# Grove-LED_Socket_Kit_v1_3.net
KiCad netlist of a schematic drawn in EAGLE
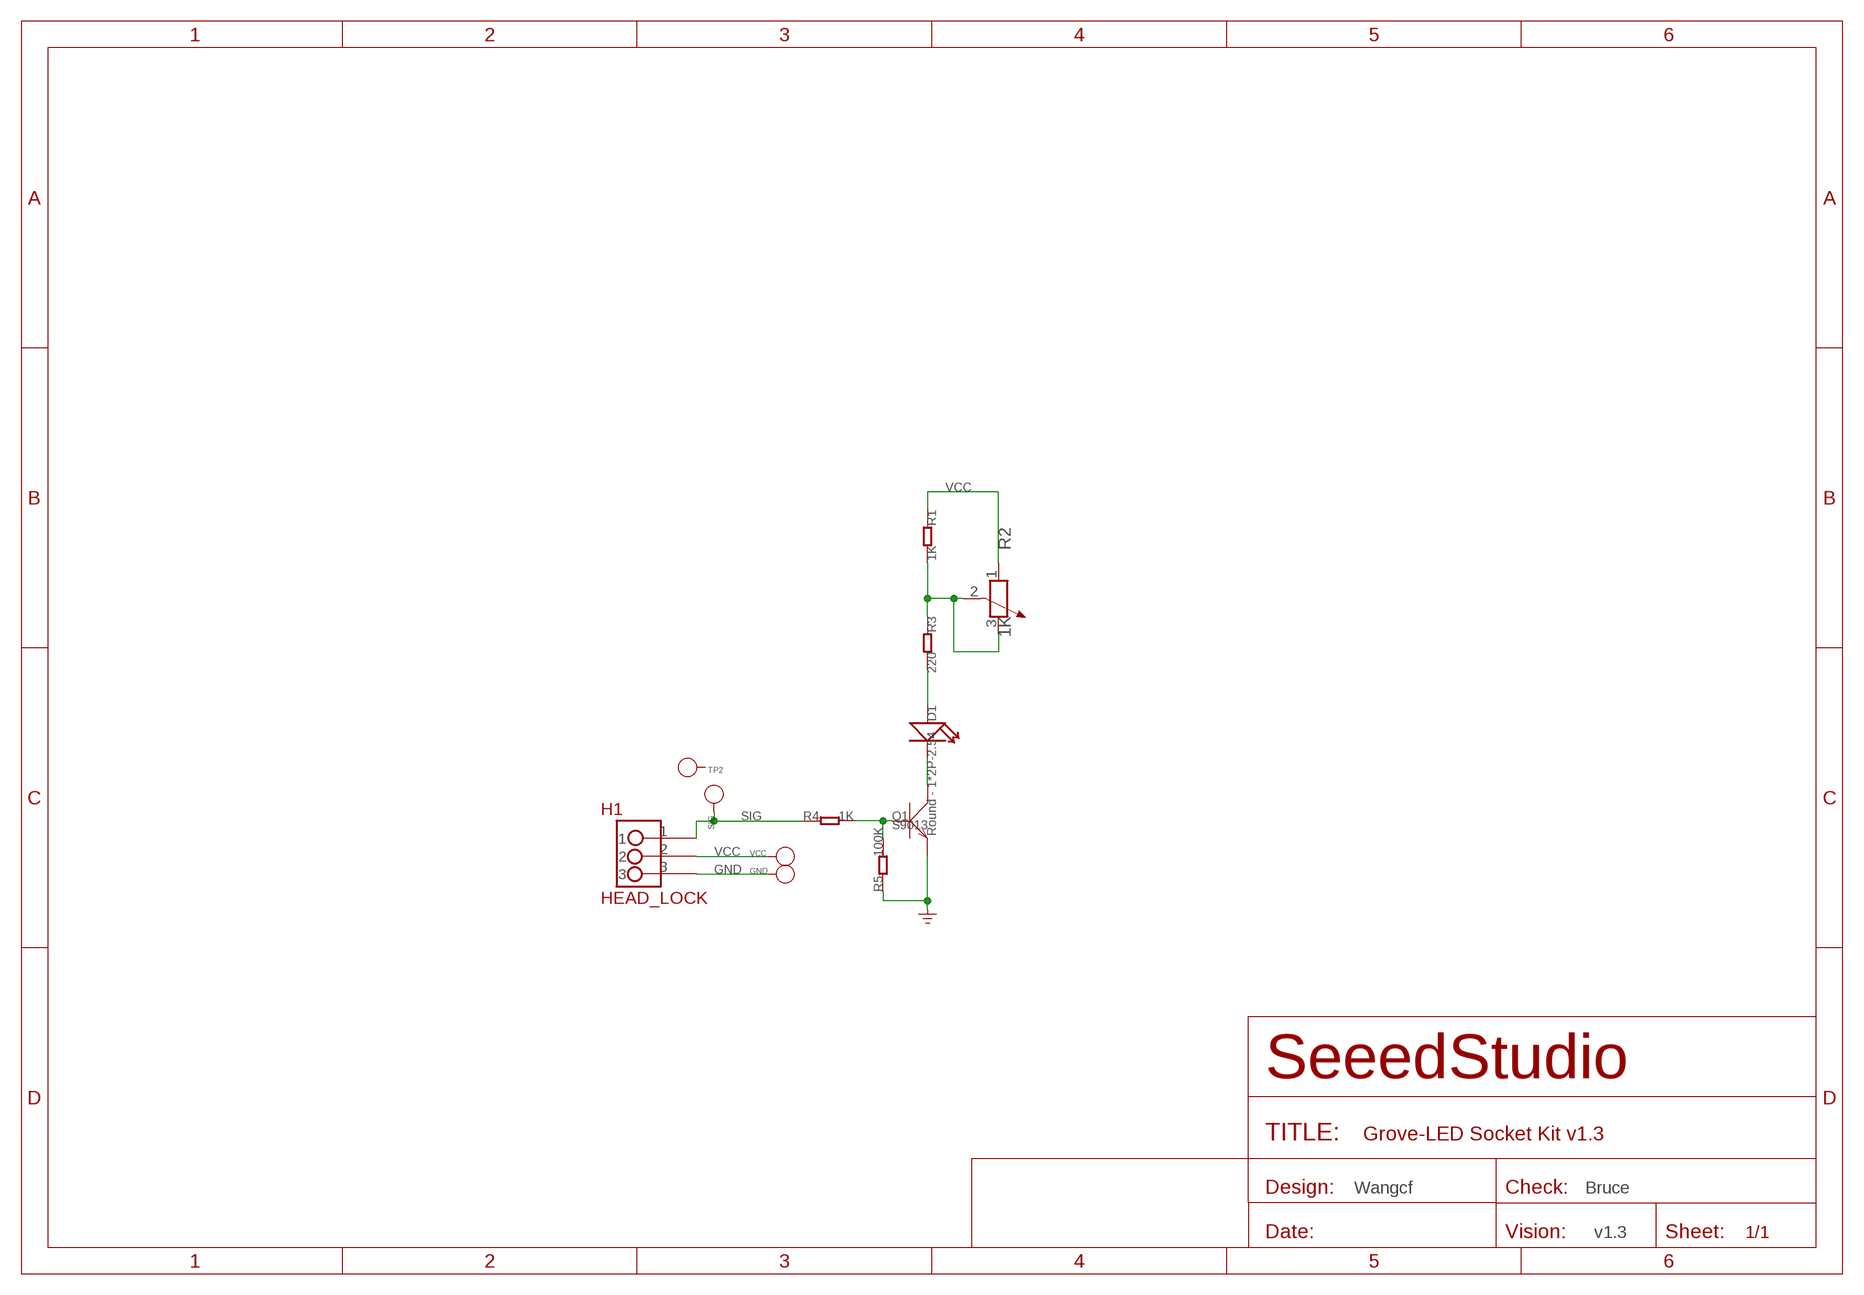
[diagram p0: schematic, sheet 1]

(export (version "E")
  (design (tool "Eeschema 10.0.6"))
  (components
    (comp (ref "D1")
      (value "Round - 1*2P-2.54")
      (footprint "eagle-import:LED-2P-2.54-6MM")
      (libsource (lib "eagle-import") (part "LED-6MM"))
    )
    (comp (ref "GND")
      (value "PAD-TEST-POINT'4545'")
      (footprint "eagle-import:TP_4545")
      (fields (field (name "PARTNO") "DNP"))
      (libsource (lib "eagle-import") (part "PAD-TEST-POINT'4545'"))
    )
    (comp (ref "H1")
      (value "HEAD_LOCK")
      (footprint "eagle-import:HEAD_LOCK")
      (libsource (lib "eagle-import") (part "HEAD_LOCK"))
    )
    (comp (ref "Q1")
      (value "S9013")
      (footprint "eagle-import:SOT23")
      (libsource (lib "eagle-import") (part "TRANSISTOR-NPN-SOT23"))
    )
    (comp (ref "R1")
      (value "1K")
      (footprint "eagle-import:0603")
      (libsource (lib "eagle-import") (part "005-R0603"))
    )
    (comp (ref "R2")
      (value "1K")
      (footprint "eagle-import:3P-SQUA-6.7X6.4")
      (libsource (lib "eagle-import") (part "R-POTENTIOMETER'EVN-D8A-A03-B'"))
    )
    (comp (ref "R3")
      (value "220")
      (footprint "eagle-import:0603")
      (libsource (lib "eagle-import") (part "005-R0603"))
    )
    (comp (ref "R4")
      (value "1K")
      (footprint "eagle-import:0603")
      (libsource (lib "eagle-import") (part "005-R0603"))
    )
    (comp (ref "R5")
      (value "100K")
      (footprint "eagle-import:0603")
      (libsource (lib "eagle-import") (part "005-R0603"))
    )
    (comp (ref "SIG")
      (value "PAD-TEST-POINT'4545'")
      (footprint "eagle-import:TP_4545")
      (fields (field (name "PARTNO") "DNP"))
      (libsource (lib "eagle-import") (part "PAD-TEST-POINT'4545'"))
    )
    (comp (ref "TP2")
      (value "PAD-TEST-POINT'4545'")
      (footprint "eagle-import:TP_4545")
      (fields (field (name "PARTNO") "DNP"))
      (libsource (lib "eagle-import") (part "PAD-TEST-POINT'4545'"))
    )
    (comp (ref "VCC")
      (value "PAD-TEST-POINT'4545'")
      (footprint "eagle-import:TP_4545")
      (fields (field (name "PARTNO") "DNP"))
      (libsource (lib "eagle-import") (part "PAD-TEST-POINT'4545'"))
    )
  )
  (nets
    (net (code "1") (name "/SIG") (class "Default")
      (node (ref "H1") (pin "1") (pinfunction "1_1") (pintype "passive"))
      (node (ref "R4") (pin "1") (pinfunction "1_1") (pintype "passive"))
      (node (ref "SIG") (pin "T") (pinfunction "T_T") (pintype "bidirectional"))
    )
    (net (code "2") (name "/VCC") (class "Default")
      (node (ref "H1") (pin "2") (pinfunction "2_2") (pintype "passive"))
      (node (ref "R1") (pin "1") (pinfunction "1_1") (pintype "passive"))
      (node (ref "R2") (pin "1") (pinfunction "1_1") (pintype "passive"))
      (node (ref "VCC") (pin "T") (pinfunction "T_T") (pintype "bidirectional"))
    )
    (net (code "3") (name "GND_POWER") (class "Default")
      (node (ref "GND") (pin "T") (pinfunction "T_T") (pintype "bidirectional"))
      (node (ref "H1") (pin "3") (pinfunction "3_3") (pintype "passive"))
      (node (ref "Q1") (pin "2") (pinfunction "E_2") (pintype "passive"))
      (node (ref "R5") (pin "1") (pinfunction "1_1") (pintype "passive"))
    )
    (net (code "4") (name "Net-(D1-Pad+)") (class "Default")
      (node (ref "D1") (pin "+") (pinfunction "+_+") (pintype "passive"))
      (node (ref "R3") (pin "2") (pinfunction "2_2") (pintype "passive"))
    )
    (net (code "5") (name "Net-(Q1-B)") (class "Default")
      (node (ref "Q1") (pin "1") (pinfunction "B_1") (pintype "passive"))
      (node (ref "R4") (pin "2") (pinfunction "2_2") (pintype "passive"))
      (node (ref "R5") (pin "2") (pinfunction "2_2") (pintype "passive"))
    )
    (net (code "6") (name "Net-(Q1-C)") (class "Default")
      (node (ref "D1") (pin "-") (pinfunction "-_-") (pintype "passive"))
      (node (ref "Q1") (pin "3") (pinfunction "C_3") (pintype "passive"))
    )
    (net (code "7") (name "Net-(R2-2)") (class "Default")
      (node (ref "R1") (pin "2") (pinfunction "2_2") (pintype "passive"))
      (node (ref "R2") (pin "2") (pinfunction "3_2") (pintype "passive"))
      (node (ref "R2") (pin "3") (pinfunction "2_3") (pintype "passive"))
      (node (ref "R3") (pin "1") (pinfunction "1_1") (pintype "passive"))
    )
    (net (code "8") (name "unconnected-(TP2-PadT)") (class "Default")
      (node (ref "TP2") (pin "T") (pinfunction "T_T") (pintype "bidirectional"))
    )
  )
)
